# H-00488_-_USB_Hub.net
KiCad netlist of a schematic drawn in Altium Designer
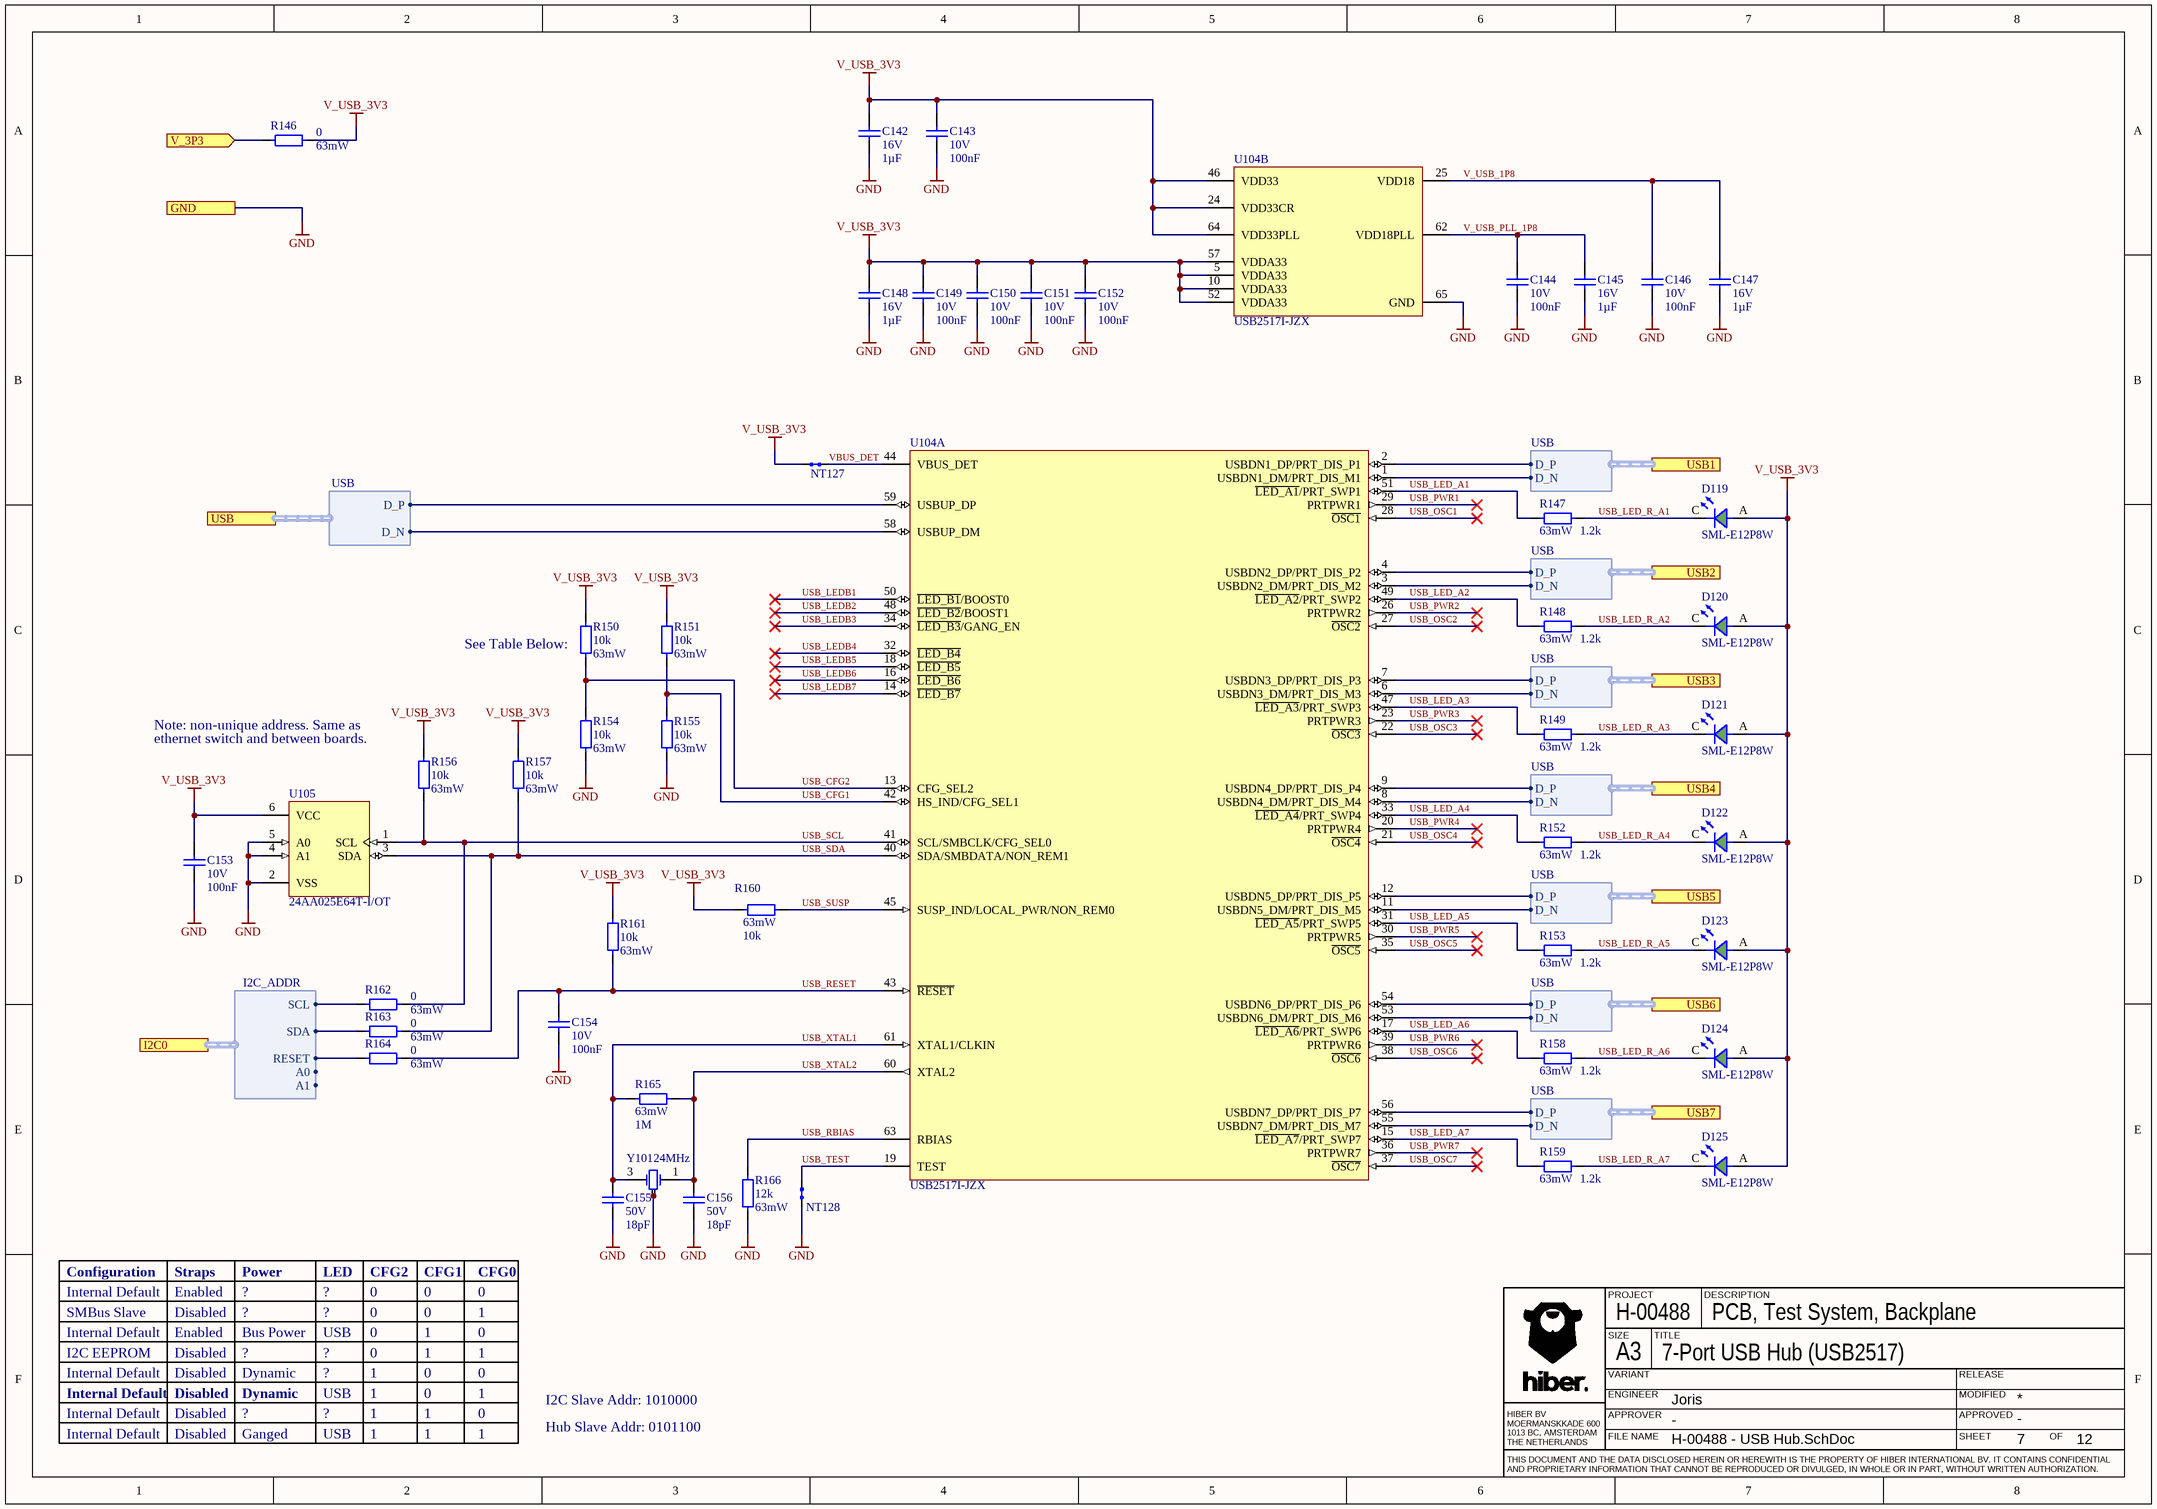
[diagram p0: H-00488 - USB Hub.SchDoc]

(export (version "E")
  (design (tool "Eeschema 10.0.6"))
  (components
    (comp (ref "C142")
      (value "1µF")
      (footprint "CAPC100X50X55L30N")
      (description "CAP Standard 0402 (1005) 1,0uF 16V X5R (Standard)")
      (fields
        (field (name "RATED VOLTAGE") "16V")
        (field (name "TOLERANCE") "10%")
        (field (name "Comment") "C0402C105K4PACTU")
      )
      (libsource (lib "Hiber") (part "CAPACITOR"))
    )
    (comp (ref "C143")
      (value "100nF")
      (footprint "CAPC100X50X55L30N")
      (description "CAP Standard 0402 (1005) 100,0nF 10V X7R (Standard)")
      (fields
        (field (name "RATED VOLTAGE") "10V")
        (field (name "TOLERANCE") "10%")
        (field (name "Comment") "C0402C104K8RACTU")
      )
      (libsource (lib "Hiber Vault") (part "CAPACITOR"))
    )
    (comp (ref "C144")
      (value "100nF")
      (footprint "CAPC100X50X55L30N")
      (description "CAP Standard 0402 (1005) 100,0nF 10V X7R (Standard)")
      (fields
        (field (name "RATED VOLTAGE") "10V")
        (field (name "TOLERANCE") "10%")
        (field (name "Comment") "C0402C104K8RACTU")
      )
      (libsource (lib "Hiber Vault") (part "CAPACITOR"))
    )
    (comp (ref "C145")
      (value "1µF")
      (footprint "CAPC100X50X55L30N")
      (description "CAP Standard 0402 (1005) 1,0uF 16V X5R (Standard)")
      (fields
        (field (name "RATED VOLTAGE") "16V")
        (field (name "TOLERANCE") "10%")
        (field (name "Comment") "C0402C105K4PACTU")
      )
      (libsource (lib "Hiber") (part "CAPACITOR"))
    )
    (comp (ref "C146")
      (value "100nF")
      (footprint "CAPC100X50X55L30N")
      (description "CAP Standard 0402 (1005) 100,0nF 10V X7R (Standard)")
      (fields
        (field (name "RATED VOLTAGE") "10V")
        (field (name "TOLERANCE") "10%")
        (field (name "Comment") "C0402C104K8RACTU")
      )
      (libsource (lib "Hiber Vault") (part "CAPACITOR"))
    )
    (comp (ref "C147")
      (value "1µF")
      (footprint "CAPC100X50X55L30N")
      (description "CAP Standard 0402 (1005) 1,0uF 16V X5R (Standard)")
      (fields
        (field (name "RATED VOLTAGE") "16V")
        (field (name "TOLERANCE") "10%")
        (field (name "Comment") "C0402C105K4PACTU")
      )
      (libsource (lib "Hiber") (part "CAPACITOR"))
    )
    (comp (ref "C148")
      (value "1µF")
      (footprint "CAPC100X50X55L30N")
      (description "CAP Standard 0402 (1005) 1,0uF 16V X5R (Standard)")
      (fields
        (field (name "RATED VOLTAGE") "16V")
        (field (name "TOLERANCE") "10%")
        (field (name "Comment") "C0402C105K4PACTU")
      )
      (libsource (lib "Hiber") (part "CAPACITOR"))
    )
    (comp (ref "C149")
      (value "100nF")
      (footprint "CAPC100X50X55L30N")
      (description "CAP Standard 0402 (1005) 100,0nF 10V X7R (Standard)")
      (fields
        (field (name "RATED VOLTAGE") "10V")
        (field (name "TOLERANCE") "10%")
        (field (name "Comment") "C0402C104K8RACTU")
      )
      (libsource (lib "Hiber Vault") (part "CAPACITOR"))
    )
    (comp (ref "C150")
      (value "100nF")
      (footprint "CAPC100X50X55L30N")
      (description "CAP Standard 0402 (1005) 100,0nF 10V X7R (Standard)")
      (fields
        (field (name "RATED VOLTAGE") "10V")
        (field (name "TOLERANCE") "10%")
        (field (name "Comment") "C0402C104K8RACTU")
      )
      (libsource (lib "Hiber Vault") (part "CAPACITOR"))
    )
    (comp (ref "C151")
      (value "100nF")
      (footprint "CAPC100X50X55L30N")
      (description "CAP Standard 0402 (1005) 100,0nF 10V X7R (Standard)")
      (fields
        (field (name "RATED VOLTAGE") "10V")
        (field (name "TOLERANCE") "10%")
        (field (name "Comment") "C0402C104K8RACTU")
      )
      (libsource (lib "Hiber Vault") (part "CAPACITOR"))
    )
    (comp (ref "C152")
      (value "100nF")
      (footprint "CAPC100X50X55L30N")
      (description "CAP Standard 0402 (1005) 100,0nF 10V X7R (Standard)")
      (fields
        (field (name "RATED VOLTAGE") "10V")
        (field (name "TOLERANCE") "10%")
        (field (name "Comment") "C0402C104K8RACTU")
      )
      (libsource (lib "Hiber Vault") (part "CAPACITOR"))
    )
    (comp (ref "C153")
      (value "100nF")
      (footprint "CAPC100X50X55L30N")
      (description "CAP Standard 0402 (1005) 100,0nF 10V X7R (Standard)")
      (fields
        (field (name "RATED VOLTAGE") "10V")
        (field (name "TOLERANCE") "10%")
        (field (name "Comment") "C0402C104K8RACTU")
      )
      (libsource (lib "Hiber Vault") (part "CAPACITOR"))
    )
    (comp (ref "C154")
      (value "100nF")
      (footprint "CAPC100X50X55L30N")
      (description "CAP Standard 0402 (1005) 100,0nF 10V X7R (Standard)")
      (fields
        (field (name "RATED VOLTAGE") "10V")
        (field (name "TOLERANCE") "10%")
        (field (name "Comment") "C0402C104K8RACTU")
      )
      (libsource (lib "Hiber Vault") (part "CAPACITOR"))
    )
    (comp (ref "C155")
      (value "18pF")
      (footprint "CAPC100X50X55L30N")
      (description "CAP Standard 0402 (1005) 18,0pF 50V C0G (Standard)")
      (fields
        (field (name "RATED VOLTAGE") "50V")
        (field (name "TOLERANCE") "5%")
        (field (name "Comment") "C0402C180J5GACTU")
      )
      (libsource (lib "Hiber") (part "CAPACITOR"))
    )
    (comp (ref "C156")
      (value "18pF")
      (footprint "CAPC100X50X55L30N")
      (description "CAP Standard 0402 (1005) 18,0pF 50V C0G (Standard)")
      (fields
        (field (name "RATED VOLTAGE") "50V")
        (field (name "TOLERANCE") "5%")
        (field (name "Comment") "C0402C180J5GACTU")
      )
      (libsource (lib "Hiber") (part "CAPACITOR"))
    )
    (comp (ref "D119")
      (value "SML-E12P8W")
      (footprint "LEDC170X80X80L20_GREEN")
      (description "LED Green Diffused 0603 SMD")
      (libsource (lib "Hiber") (part "DIODE-LED-GREEN"))
    )
    (comp (ref "D120")
      (value "SML-E12P8W")
      (footprint "LEDC170X80X80L20_GREEN")
      (description "LED Green Diffused 0603 SMD")
      (libsource (lib "Hiber") (part "DIODE-LED-GREEN"))
    )
    (comp (ref "D121")
      (value "SML-E12P8W")
      (footprint "LEDC170X80X80L20_GREEN")
      (description "LED Green Diffused 0603 SMD")
      (libsource (lib "Hiber") (part "DIODE-LED-GREEN"))
    )
    (comp (ref "D122")
      (value "SML-E12P8W")
      (footprint "LEDC170X80X80L20_GREEN")
      (description "LED Green Diffused 0603 SMD")
      (libsource (lib "Hiber") (part "DIODE-LED-GREEN"))
    )
    (comp (ref "D123")
      (value "SML-E12P8W")
      (footprint "LEDC170X80X80L20_GREEN")
      (description "LED Green Diffused 0603 SMD")
      (libsource (lib "Hiber") (part "DIODE-LED-GREEN"))
    )
    (comp (ref "D124")
      (value "SML-E12P8W")
      (footprint "LEDC170X80X80L20_GREEN")
      (description "LED Green Diffused 0603 SMD")
      (libsource (lib "Hiber") (part "DIODE-LED-GREEN"))
    )
    (comp (ref "D125")
      (value "SML-E12P8W")
      (footprint "LEDC170X80X80L20_GREEN")
      (description "LED Green Diffused 0603 SMD")
      (libsource (lib "Hiber") (part "DIODE-LED-GREEN"))
    )
    (comp (ref "NT127")
      (value "NET-TIE")
      (footprint "NT200")
      (description "Net Tie, Inline")
      (libsource (lib "Hiber") (part "NET-TIE"))
    )
    (comp (ref "NT128")
      (value "NET-TIE")
      (footprint "NT200")
      (description "Net Tie, Inline")
      (libsource (lib "Hiber") (part "NET-TIE"))
    )
    (comp (ref "R146")
      (value "0")
      (footprint "RESC100X50X40L25N")
      (description "RES Standard Thick Film 0402 0R00 ±1% 0,063W")
      (fields
        (field (name "TOLERANCE") "1%")
        (field (name "RATED POWER") "63mW")
        (field (name "Comment") "CRCW04020000Z0ED")
      )
      (libsource (lib "Hiber") (part "RESISTOR-2P"))
    )
    (comp (ref "R147")
      (value "1.2k")
      (footprint "RESC100X50X40L25N")
      (description "RES Standard Thick Film 0402 1K20 ±1% 0,063W")
      (fields
        (field (name "RATED POWER") "63mW")
        (field (name "TOLERANCE") "1%")
        (field (name "Comment") "CRCW04021K20FKED")
      )
      (libsource (lib "Hiber") (part "RESISTOR-2P"))
    )
    (comp (ref "R148")
      (value "1.2k")
      (footprint "RESC100X50X40L25N")
      (description "RES Standard Thick Film 0402 1K20 ±1% 0,063W")
      (fields
        (field (name "RATED POWER") "63mW")
        (field (name "TOLERANCE") "1%")
        (field (name "Comment") "CRCW04021K20FKED")
      )
      (libsource (lib "Hiber") (part "RESISTOR-2P"))
    )
    (comp (ref "R149")
      (value "1.2k")
      (footprint "RESC100X50X40L25N")
      (description "RES Standard Thick Film 0402 1K20 ±1% 0,063W")
      (fields
        (field (name "RATED POWER") "63mW")
        (field (name "TOLERANCE") "1%")
        (field (name "Comment") "CRCW04021K20FKED")
      )
      (libsource (lib "Hiber") (part "RESISTOR-2P"))
    )
    (comp (ref "R150")
      (value "10k")
      (footprint "RESC100X50X40L25N")
      (description "RES Standard Thick Film 0402 10K0 ±1% 0,063W")
      (fields
        (field (name "TOLERANCE") "1%")
        (field (name "RATED POWER") "63mW")
        (field (name "Comment") "CRCW040210K0FKED")
      )
      (libsource (lib "Hiber") (part "RESISTOR-2P"))
    )
    (comp (ref "R151")
      (value "10k")
      (footprint "RESC100X50X40L25N")
      (description "RES Standard Thick Film 0402 10K0 ±1% 0,063W")
      (fields
        (field (name "TOLERANCE") "1%")
        (field (name "RATED POWER") "63mW")
        (field (name "Comment") "CRCW040210K0FKED")
      )
      (libsource (lib "Hiber") (part "RESISTOR-2P"))
    )
    (comp (ref "R152")
      (value "1.2k")
      (footprint "RESC100X50X40L25N")
      (description "RES Standard Thick Film 0402 1K20 ±1% 0,063W")
      (fields
        (field (name "RATED POWER") "63mW")
        (field (name "TOLERANCE") "1%")
        (field (name "Comment") "CRCW04021K20FKED")
      )
      (libsource (lib "Hiber") (part "RESISTOR-2P"))
    )
    (comp (ref "R153")
      (value "1.2k")
      (footprint "RESC100X50X40L25N")
      (description "RES Standard Thick Film 0402 1K20 ±1% 0,063W")
      (fields
        (field (name "RATED POWER") "63mW")
        (field (name "TOLERANCE") "1%")
        (field (name "Comment") "CRCW04021K20FKED")
      )
      (libsource (lib "Hiber") (part "RESISTOR-2P"))
    )
    (comp (ref "R154")
      (value "10k")
      (footprint "RESC100X50X40L25N")
      (description "RES Standard Thick Film 0402 10K0 ±1% 0,063W")
      (fields
        (field (name "TOLERANCE") "1%")
        (field (name "RATED POWER") "63mW")
        (field (name "Comment") "CRCW040210K0FKED")
      )
      (libsource (lib "Hiber") (part "RESISTOR-2P"))
    )
    (comp (ref "R155")
      (value "10k")
      (footprint "RESC100X50X40L25N")
      (description "RES Standard Thick Film 0402 10K0 ±1% 0,063W")
      (fields
        (field (name "TOLERANCE") "1%")
        (field (name "RATED POWER") "63mW")
        (field (name "Comment") "CRCW040210K0FKED")
      )
      (libsource (lib "Hiber") (part "RESISTOR-2P"))
    )
    (comp (ref "R156")
      (value "10k")
      (footprint "RESC100X50X40L25N")
      (description "RES Standard Thick Film 0402 10K0 ±1% 0,063W")
      (fields
        (field (name "TOLERANCE") "1%")
        (field (name "RATED POWER") "63mW")
        (field (name "Comment") "CRCW040210K0FKED")
      )
      (libsource (lib "Hiber") (part "RESISTOR-2P"))
    )
    (comp (ref "R157")
      (value "10k")
      (footprint "RESC100X50X40L25N")
      (description "RES Standard Thick Film 0402 10K0 ±1% 0,063W")
      (fields
        (field (name "TOLERANCE") "1%")
        (field (name "RATED POWER") "63mW")
        (field (name "Comment") "CRCW040210K0FKED")
      )
      (libsource (lib "Hiber") (part "RESISTOR-2P"))
    )
    (comp (ref "R158")
      (value "1.2k")
      (footprint "RESC100X50X40L25N")
      (description "RES Standard Thick Film 0402 1K20 ±1% 0,063W")
      (fields
        (field (name "RATED POWER") "63mW")
        (field (name "TOLERANCE") "1%")
        (field (name "Comment") "CRCW04021K20FKED")
      )
      (libsource (lib "Hiber") (part "RESISTOR-2P"))
    )
    (comp (ref "R159")
      (value "1.2k")
      (footprint "RESC100X50X40L25N")
      (description "RES Standard Thick Film 0402 1K20 ±1% 0,063W")
      (fields
        (field (name "RATED POWER") "63mW")
        (field (name "TOLERANCE") "1%")
        (field (name "Comment") "CRCW04021K20FKED")
      )
      (libsource (lib "Hiber") (part "RESISTOR-2P"))
    )
    (comp (ref "R160")
      (value "10k")
      (footprint "RESC100X50X40L25N")
      (description "RES Standard Thick Film 0402 10K0 ±1% 0,063W")
      (fields
        (field (name "TOLERANCE") "1%")
        (field (name "RATED POWER") "63mW")
        (field (name "Comment") "CRCW040210K0FKED")
      )
      (libsource (lib "Hiber") (part "RESISTOR-2P"))
    )
    (comp (ref "R161")
      (value "10k")
      (footprint "RESC100X50X40L25N")
      (description "RES Standard Thick Film 0402 10K0 ±1% 0,063W")
      (fields
        (field (name "TOLERANCE") "1%")
        (field (name "RATED POWER") "63mW")
        (field (name "Comment") "CRCW040210K0FKED")
      )
      (libsource (lib "Hiber") (part "RESISTOR-2P"))
    )
    (comp (ref "R162")
      (value "0")
      (footprint "RESC100X50X40L25N")
      (description "RES Standard Thick Film 0402 0R00 ±1% 0,063W")
      (fields
        (field (name "TOLERANCE") "1%")
        (field (name "RATED POWER") "63mW")
        (field (name "Comment") "CRCW04020000Z0ED")
      )
      (libsource (lib "Hiber") (part "RESISTOR-2P"))
    )
    (comp (ref "R163")
      (value "0")
      (footprint "RESC100X50X40L25N")
      (description "RES Standard Thick Film 0402 0R00 ±1% 0,063W")
      (fields
        (field (name "TOLERANCE") "1%")
        (field (name "RATED POWER") "63mW")
        (field (name "Comment") "CRCW04020000Z0ED")
      )
      (libsource (lib "Hiber") (part "RESISTOR-2P"))
    )
    (comp (ref "R164")
      (value "0")
      (footprint "RESC100X50X40L25N")
      (description "RES Standard Thick Film 0402 0R00 ±1% 0,063W")
      (fields
        (field (name "TOLERANCE") "1%")
        (field (name "RATED POWER") "63mW")
        (field (name "Comment") "CRCW04020000Z0ED")
      )
      (libsource (lib "Hiber") (part "RESISTOR-2P"))
    )
    (comp (ref "R165")
      (value "1M")
      (footprint "RESC100X50X40L25N")
      (description "RES Standard Thick Film 0402 1M00 ±1% 0,063W")
      (fields
        (field (name "RATED POWER") "63mW")
        (field (name "TOLERANCE") "1%")
        (field (name "Comment") "CRCW04021M00FKED")
      )
      (libsource (lib "Hiber") (part "RESISTOR-2P"))
    )
    (comp (ref "R166")
      (value "12k")
      (footprint "RESC100X50X40L25N")
      (description "RES Standard Thick Film 0402 12K0 ±1% 0,063W")
      (fields
        (field (name "TOLERANCE") "1%")
        (field (name "RATED POWER") "63mW")
        (field (name "Comment") "CRCW040212K0FKED")
      )
      (libsource (lib "Hiber") (part "RESISTOR-2P"))
    )
    (comp (ref "U104")
      (value "USB2517I-JZX")
      (footprint "QFN65P50_900X900X100L40X24T470N")
      (description "USB Bus Controller, CMOS")
      (libsource (lib "Hiber") (part "USB2517"))
    )
    (comp (ref "U105")
      (value "24AA025E64T-I/OT")
      (footprint "SOT23-6P95_270X145L35X35")
      (description "EEPROM, 256X8, Serial, CMOS, PDSO5")
      (libsource (lib "Hiber") (part "MCHP-24AA025E64_025UID-SOT-23-6"))
    )
    (comp (ref "Y101")
      (value "TSX-322524.0000MF15X-AC3")
      (footprint "OSCCC320X250X60L90X110")
      (description "Parallel - Fundamental Quartz Crystal, 24MHz Nom")
      (fields (field (name "FREQUENCY") "24MHz") (field (name "TOLERANCE") "10ppm"))
      (libsource (lib "Hiber") (part "CRYSTAL-4P"))
    )
  )
  (nets
    (net (code "3") (name "/RESET") (class "Default")
      (node (ref "R164") (pin "1") (pinfunction "1_1") (pintype "passive"))
    )
    (net (code "4") (name "/SCL") (class "Default")
      (node (ref "R162") (pin "1") (pinfunction "1_1") (pintype "passive"))
    )
    (net (code "5") (name "/SDA") (class "Default")
      (node (ref "R163") (pin "2") (pinfunction "2_2") (pintype "passive"))
    )
    (net (code "6") (name "/USB_CFG1") (class "Default")
      (node (ref "R151") (pin "2") (pinfunction "2_2") (pintype "passive"))
      (node (ref "R155") (pin "1") (pinfunction "1_1") (pintype "passive"))
      (node (ref "U104") (pin "42") (pinfunction "HS_IND/CFG_SEL1_42") (pintype "bidirectional"))
    )
    (net (code "7") (name "/USB_CFG2") (class "Default")
      (node (ref "R150") (pin "2") (pinfunction "2_2") (pintype "passive"))
      (node (ref "R154") (pin "1") (pinfunction "1_1") (pintype "passive"))
      (node (ref "U104") (pin "13") (pinfunction "CFG_SEL2_13") (pintype "bidirectional"))
    )
    (net (code "8") (name "/USB_LEDB1") (class "Default")
      (node (ref "U104") (pin "50") (pinfunction "~{LED_B1}/BOOST0_50") (pintype "bidirectional+no_connect"))
    )
    (net (code "9") (name "/USB_LEDB2") (class "Default")
      (node (ref "U104") (pin "48") (pinfunction "~{LED_B2}/BOOST1_48") (pintype "bidirectional+no_connect"))
    )
    (net (code "10") (name "/USB_LEDB3") (class "Default")
      (node (ref "U104") (pin "34") (pinfunction "~{LED_B3}/GANG_EN_34") (pintype "bidirectional+no_connect"))
    )
    (net (code "11") (name "/USB_LEDB4") (class "Default")
      (node (ref "U104") (pin "32") (pinfunction "~{LED_B4}_32") (pintype "bidirectional+no_connect"))
    )
    (net (code "12") (name "/USB_LEDB5") (class "Default")
      (node (ref "U104") (pin "18") (pinfunction "~{LED_B5}_18") (pintype "bidirectional+no_connect"))
    )
    (net (code "13") (name "/USB_LEDB6") (class "Default")
      (node (ref "U104") (pin "16") (pinfunction "~{LED_B6}_16") (pintype "bidirectional+no_connect"))
    )
    (net (code "14") (name "/USB_LEDB7") (class "Default")
      (node (ref "U104") (pin "14") (pinfunction "~{LED_B7}_14") (pintype "bidirectional+no_connect"))
    )
    (net (code "15") (name "/USB_LED_A1") (class "Default")
      (node (ref "R147") (pin "2") (pinfunction "2_2") (pintype "passive"))
      (node (ref "U104") (pin "51") (pinfunction "~{LED_A1}/PRT_SWP1_51") (pintype "bidirectional"))
    )
    (net (code "16") (name "/USB_LED_A2") (class "Default")
      (node (ref "R148") (pin "2") (pinfunction "2_2") (pintype "passive"))
      (node (ref "U104") (pin "49") (pinfunction "~{LED_A2}/PRT_SWP2_49") (pintype "bidirectional"))
    )
    (net (code "17") (name "/USB_LED_A3") (class "Default")
      (node (ref "R149") (pin "2") (pinfunction "2_2") (pintype "passive"))
      (node (ref "U104") (pin "47") (pinfunction "~{LED_A3}/PRT_SWP3_47") (pintype "bidirectional"))
    )
    (net (code "18") (name "/USB_LED_A4") (class "Default")
      (node (ref "R152") (pin "2") (pinfunction "2_2") (pintype "passive"))
      (node (ref "U104") (pin "33") (pinfunction "~{LED_A4}/PRT_SWP4_33") (pintype "bidirectional"))
    )
    (net (code "19") (name "/USB_LED_A5") (class "Default")
      (node (ref "R153") (pin "2") (pinfunction "2_2") (pintype "passive"))
      (node (ref "U104") (pin "31") (pinfunction "~{LED_A5}/PRT_SWP5_31") (pintype "bidirectional"))
    )
    (net (code "20") (name "/USB_LED_A6") (class "Default")
      (node (ref "R158") (pin "2") (pinfunction "2_2") (pintype "passive"))
      (node (ref "U104") (pin "17") (pinfunction "~{LED_A6}/PRT_SWP6_17") (pintype "bidirectional"))
    )
    (net (code "21") (name "/USB_LED_A7") (class "Default")
      (node (ref "R159") (pin "2") (pinfunction "2_2") (pintype "passive"))
      (node (ref "U104") (pin "15") (pinfunction "~{LED_A7}/PRT_SWP7_15") (pintype "bidirectional"))
    )
    (net (code "22") (name "/USB_LED_R_A1") (class "Default")
      (node (ref "D119") (pin "C") (pinfunction "C_C") (pintype "passive"))
      (node (ref "R147") (pin "1") (pinfunction "1_1") (pintype "passive"))
    )
    (net (code "23") (name "/USB_LED_R_A2") (class "Default")
      (node (ref "D120") (pin "C") (pinfunction "C_C") (pintype "passive"))
      (node (ref "R148") (pin "1") (pinfunction "1_1") (pintype "passive"))
    )
    (net (code "24") (name "/USB_LED_R_A3") (class "Default")
      (node (ref "D121") (pin "C") (pinfunction "C_C") (pintype "passive"))
      (node (ref "R149") (pin "1") (pinfunction "1_1") (pintype "passive"))
    )
    (net (code "25") (name "/USB_LED_R_A4") (class "Default")
      (node (ref "D122") (pin "C") (pinfunction "C_C") (pintype "passive"))
      (node (ref "R152") (pin "1") (pinfunction "1_1") (pintype "passive"))
    )
    (net (code "26") (name "/USB_LED_R_A5") (class "Default")
      (node (ref "D123") (pin "C") (pinfunction "C_C") (pintype "passive"))
      (node (ref "R153") (pin "1") (pinfunction "1_1") (pintype "passive"))
    )
    (net (code "27") (name "/USB_LED_R_A6") (class "Default")
      (node (ref "D124") (pin "C") (pinfunction "C_C") (pintype "passive"))
      (node (ref "R158") (pin "1") (pinfunction "1_1") (pintype "passive"))
    )
    (net (code "28") (name "/USB_LED_R_A7") (class "Default")
      (node (ref "D125") (pin "C") (pinfunction "C_C") (pintype "passive"))
      (node (ref "R159") (pin "1") (pinfunction "1_1") (pintype "passive"))
    )
    (net (code "29") (name "/USB_OSC1") (class "Default")
      (node (ref "U104") (pin "28") (pinfunction "~{OSC1}_28") (pintype "input+no_connect"))
    )
    (net (code "30") (name "/USB_OSC2") (class "Default")
      (node (ref "U104") (pin "27") (pinfunction "~{OSC2}_27") (pintype "input+no_connect"))
    )
    (net (code "31") (name "/USB_OSC3") (class "Default")
      (node (ref "U104") (pin "22") (pinfunction "~{OSC3}_22") (pintype "input+no_connect"))
    )
    (net (code "32") (name "/USB_OSC4") (class "Default")
      (node (ref "U104") (pin "21") (pinfunction "~{OSC4}_21") (pintype "input+no_connect"))
    )
    (net (code "33") (name "/USB_OSC5") (class "Default")
      (node (ref "U104") (pin "35") (pinfunction "~{OSC5}_35") (pintype "input+no_connect"))
    )
    (net (code "34") (name "/USB_OSC6") (class "Default")
      (node (ref "U104") (pin "38") (pinfunction "~{OSC6}_38") (pintype "input+no_connect"))
    )
    (net (code "35") (name "/USB_OSC7") (class "Default")
      (node (ref "U104") (pin "37") (pinfunction "~{OSC7}_37") (pintype "input+no_connect"))
    )
    (net (code "36") (name "/USB_PWR1") (class "Default")
      (node (ref "U104") (pin "29") (pinfunction "PRTPWR1_29") (pintype "output+no_connect"))
    )
    (net (code "37") (name "/USB_PWR2") (class "Default")
      (node (ref "U104") (pin "26") (pinfunction "PRTPWR2_26") (pintype "output+no_connect"))
    )
    (net (code "38") (name "/USB_PWR3") (class "Default")
      (node (ref "U104") (pin "23") (pinfunction "PRTPWR3_23") (pintype "output+no_connect"))
    )
    (net (code "39") (name "/USB_PWR4") (class "Default")
      (node (ref "U104") (pin "20") (pinfunction "PRTPWR4_20") (pintype "output+no_connect"))
    )
    (net (code "40") (name "/USB_PWR5") (class "Default")
      (node (ref "U104") (pin "30") (pinfunction "PRTPWR5_30") (pintype "output+no_connect"))
    )
    (net (code "41") (name "/USB_PWR6") (class "Default")
      (node (ref "U104") (pin "39") (pinfunction "PRTPWR6_39") (pintype "output+no_connect"))
    )
    (net (code "42") (name "/USB_PWR7") (class "Default")
      (node (ref "U104") (pin "36") (pinfunction "PRTPWR7_36") (pintype "output+no_connect"))
    )
    (net (code "43") (name "/USB_RBIAS") (class "Default")
      (node (ref "R166") (pin "2") (pinfunction "2_2") (pintype "passive"))
      (node (ref "U104") (pin "63") (pinfunction "RBIAS_63") (pintype "passive"))
    )
    (net (code "44") (name "/USB_RESET") (class "Default")
      (node (ref "C154") (pin "1") (pinfunction "1_1") (pintype "passive"))
      (node (ref "R161") (pin "2") (pinfunction "2_2") (pintype "passive"))
      (node (ref "R164") (pin "2") (pinfunction "2_2") (pintype "passive"))
      (node (ref "U104") (pin "43") (pinfunction "~{RESET}_43") (pintype "input"))
    )
    (net (code "45") (name "/USB_SCL") (class "Default")
      (node (ref "R156") (pin "2") (pinfunction "2_2") (pintype "passive"))
      (node (ref "R162") (pin "2") (pinfunction "2_2") (pintype "passive"))
      (node (ref "U104") (pin "41") (pinfunction "SCL/SMBCLK/CFG_SEL0_41") (pintype "bidirectional"))
      (node (ref "U105") (pin "1") (pinfunction "SCL_1") (pintype "input"))
    )
    (net (code "46") (name "/USB_SDA") (class "Default")
      (node (ref "R157") (pin "2") (pinfunction "2_2") (pintype "passive"))
      (node (ref "R163") (pin "1") (pinfunction "1_1") (pintype "passive"))
      (node (ref "U104") (pin "40") (pinfunction "SDA/SMBDATA/NON_REM1_40") (pintype "bidirectional"))
      (node (ref "U105") (pin "3") (pinfunction "SDA_3") (pintype "bidirectional"))
    )
    (net (code "47") (name "/USB_SUSP") (class "Default")
      (node (ref "R160") (pin "2") (pinfunction "2_2") (pintype "passive"))
      (node (ref "U104") (pin "45") (pinfunction "SUSP_IND/LOCAL_PWR/NON_REM0_45") (pintype "input"))
    )
    (net (code "48") (name "/USB_TEST") (class "Default")
      (node (ref "NT128") (pin "1") (pinfunction "1_1") (pintype "passive"))
      (node (ref "U104") (pin "19") (pinfunction "TEST_19") (pintype "passive"))
    )
    (net (code "49") (name "/USB_XTAL1") (class "Default")
      (node (ref "C155") (pin "1") (pinfunction "1_1") (pintype "passive"))
      (node (ref "R165") (pin "1") (pinfunction "1_1") (pintype "passive"))
      (node (ref "U104") (pin "61") (pinfunction "XTAL1/CLKIN_61") (pintype "input"))
      (node (ref "Y101") (pin "3") (pinfunction "3_3") (pintype "passive"))
    )
    (net (code "50") (name "/USB_XTAL2") (class "Default")
      (node (ref "C156") (pin "1") (pinfunction "1_1") (pintype "passive"))
      (node (ref "R165") (pin "2") (pinfunction "2_2") (pintype "passive"))
      (node (ref "U104") (pin "60") (pinfunction "XTAL2_60") (pintype "output"))
      (node (ref "Y101") (pin "1") (pinfunction "1_1") (pintype "passive"))
    )
    (net (code "51") (name "/VBUS_DET") (class "Default")
      (node (ref "NT127") (pin "2") (pinfunction "1_2") (pintype "passive"))
      (node (ref "U104") (pin "44") (pinfunction "VBUS_DET_44") (pintype "power_in"))
    )
    (net (code "52") (name "/V_3P3") (class "Default")
      (node (ref "R146") (pin "1") (pinfunction "1_1") (pintype "passive"))
    )
    (net (code "53") (name "/V_USB_1P8") (class "Default")
      (node (ref "C146") (pin "1") (pinfunction "1_1") (pintype "passive"))
      (node (ref "C147") (pin "2") (pinfunction "2_2") (pintype "passive"))
      (node (ref "U104") (pin "25") (pinfunction "VDD18_25") (pintype "power_in"))
    )
    (net (code "54") (name "/V_USB_PLL_1P8") (class "Default")
      (node (ref "C144") (pin "1") (pinfunction "1_1") (pintype "passive"))
      (node (ref "C145") (pin "2") (pinfunction "2_2") (pintype "passive"))
      (node (ref "U104") (pin "62") (pinfunction "VDD18PLL_62") (pintype "power_in"))
    )
    (net (code "57") (name "GND") (class "Default")
      (node (ref "C142") (pin "1") (pinfunction "1_1") (pintype "passive"))
      (node (ref "C143") (pin "2") (pinfunction "2_2") (pintype "passive"))
      (node (ref "C144") (pin "2") (pinfunction "2_2") (pintype "passive"))
      (node (ref "C145") (pin "1") (pinfunction "1_1") (pintype "passive"))
      (node (ref "C146") (pin "2") (pinfunction "2_2") (pintype "passive"))
      (node (ref "C147") (pin "1") (pinfunction "1_1") (pintype "passive"))
      (node (ref "C148") (pin "1") (pinfunction "1_1") (pintype "passive"))
      (node (ref "C149") (pin "2") (pinfunction "2_2") (pintype "passive"))
      (node (ref "C150") (pin "2") (pinfunction "2_2") (pintype "passive"))
      (node (ref "C151") (pin "2") (pinfunction "2_2") (pintype "passive"))
      (node (ref "C152") (pin "2") (pinfunction "2_2") (pintype "passive"))
      (node (ref "C153") (pin "2") (pinfunction "2_2") (pintype "passive"))
      (node (ref "C154") (pin "2") (pinfunction "2_2") (pintype "passive"))
      (node (ref "C155") (pin "2") (pinfunction "2_2") (pintype "passive"))
      (node (ref "C156") (pin "2") (pinfunction "2_2") (pintype "passive"))
      (node (ref "NT128") (pin "2") (pinfunction "1_2") (pintype "passive"))
      (node (ref "R154") (pin "2") (pinfunction "2_2") (pintype "passive"))
      (node (ref "R155") (pin "2") (pinfunction "2_2") (pintype "passive"))
      (node (ref "R166") (pin "1") (pinfunction "1_1") (pintype "passive"))
      (node (ref "U104") (pin "65") (pinfunction "GND_65") (pintype "power_in"))
      (node (ref "U105") (pin "2") (pinfunction "VSS_2") (pintype "power_in"))
      (node (ref "U105") (pin "4") (pinfunction "A1_4") (pintype "input"))
      (node (ref "U105") (pin "5") (pinfunction "A0_5") (pintype "input"))
      (node (ref "Y101") (pin "2") (pinfunction "2_2") (pintype "passive"))
      (node (ref "Y101") (pin "4") (pinfunction "4_4") (pintype "passive"))
    )
    (net (code "58") (name "V_USB_3V3") (class "Default")
      (node (ref "C142") (pin "2") (pinfunction "2_2") (pintype "passive"))
      (node (ref "C143") (pin "1") (pinfunction "1_1") (pintype "passive"))
      (node (ref "C148") (pin "2") (pinfunction "2_2") (pintype "passive"))
      (node (ref "C149") (pin "1") (pinfunction "1_1") (pintype "passive"))
      (node (ref "C150") (pin "1") (pinfunction "1_1") (pintype "passive"))
      (node (ref "C151") (pin "1") (pinfunction "1_1") (pintype "passive"))
      (node (ref "C152") (pin "1") (pinfunction "1_1") (pintype "passive"))
      (node (ref "C153") (pin "1") (pinfunction "1_1") (pintype "passive"))
      (node (ref "D119") (pin "A") (pinfunction "A_A") (pintype "passive"))
      (node (ref "D120") (pin "A") (pinfunction "A_A") (pintype "passive"))
      (node (ref "D121") (pin "A") (pinfunction "A_A") (pintype "passive"))
      (node (ref "D122") (pin "A") (pinfunction "A_A") (pintype "passive"))
      (node (ref "D123") (pin "A") (pinfunction "A_A") (pintype "passive"))
      (node (ref "D124") (pin "A") (pinfunction "A_A") (pintype "passive"))
      (node (ref "D125") (pin "A") (pinfunction "A_A") (pintype "passive"))
      (node (ref "NT127") (pin "1") (pinfunction "1_1") (pintype "passive"))
      (node (ref "R146") (pin "2") (pinfunction "2_2") (pintype "passive"))
      (node (ref "R150") (pin "1") (pinfunction "1_1") (pintype "passive"))
      (node (ref "R151") (pin "1") (pinfunction "1_1") (pintype "passive"))
      (node (ref "R156") (pin "1") (pinfunction "1_1") (pintype "passive"))
      (node (ref "R157") (pin "1") (pinfunction "1_1") (pintype "passive"))
      (node (ref "R160") (pin "1") (pinfunction "1_1") (pintype "passive"))
      (node (ref "R161") (pin "1") (pinfunction "1_1") (pintype "passive"))
      (node (ref "U104") (pin "10") (pinfunction "VDDA33_10") (pintype "power_in"))
      (node (ref "U104") (pin "24") (pinfunction "VDD33CR_24") (pintype "power_in"))
      (node (ref "U104") (pin "46") (pinfunction "VDD33_46") (pintype "power_in"))
      (node (ref "U104") (pin "5") (pinfunction "VDDA33_5") (pintype "power_in"))
      (node (ref "U104") (pin "52") (pinfunction "VDDA33_52") (pintype "power_in"))
      (node (ref "U104") (pin "57") (pinfunction "VDDA33_57") (pintype "power_in"))
      (node (ref "U104") (pin "64") (pinfunction "VDD33PLL_64") (pintype "power_in"))
      (node (ref "U105") (pin "6") (pinfunction "VCC_6") (pintype "power_in"))
    )
    (net (code "59") (name "unconnected-(U104A-USBDN1_DM{slash}PRT_DIS_M1-Pad1)") (class "Default")
      (node (ref "U104") (pin "1") (pinfunction "USBDN1_DM/PRT_DIS_M1_1") (pintype "bidirectional"))
    )
    (net (code "60") (name "unconnected-(U104A-USBDN1_DP{slash}PRT_DIS_P1-Pad2)") (class "Default")
      (node (ref "U104") (pin "2") (pinfunction "USBDN1_DP/PRT_DIS_P1_2") (pintype "bidirectional"))
    )
    (net (code "61") (name "unconnected-(U104A-USBDN2_DM{slash}PRT_DIS_M2-Pad3)") (class "Default")
      (node (ref "U104") (pin "3") (pinfunction "USBDN2_DM/PRT_DIS_M2_3") (pintype "bidirectional"))
    )
    (net (code "62") (name "unconnected-(U104A-USBDN2_DP{slash}PRT_DIS_P2-Pad4)") (class "Default")
      (node (ref "U104") (pin "4") (pinfunction "USBDN2_DP/PRT_DIS_P2_4") (pintype "bidirectional"))
    )
    (net (code "63") (name "unconnected-(U104A-USBDN3_DM{slash}PRT_DIS_M3-Pad6)") (class "Default")
      (node (ref "U104") (pin "6") (pinfunction "USBDN3_DM/PRT_DIS_M3_6") (pintype "bidirectional"))
    )
    (net (code "64") (name "unconnected-(U104A-USBDN3_DP{slash}PRT_DIS_P3-Pad7)") (class "Default")
      (node (ref "U104") (pin "7") (pinfunction "USBDN3_DP/PRT_DIS_P3_7") (pintype "bidirectional"))
    )
    (net (code "65") (name "unconnected-(U104A-USBDN4_DM{slash}PRT_DIS_M4-Pad8)") (class "Default")
      (node (ref "U104") (pin "8") (pinfunction "USBDN4_DM/PRT_DIS_M4_8") (pintype "bidirectional"))
    )
    (net (code "66") (name "unconnected-(U104A-USBDN4_DP{slash}PRT_DIS_P4-Pad9)") (class "Default")
      (node (ref "U104") (pin "9") (pinfunction "USBDN4_DP/PRT_DIS_P4_9") (pintype "bidirectional"))
    )
    (net (code "67") (name "unconnected-(U104A-USBDN5_DM{slash}PRT_DIS_M5-Pad11)") (class "Default")
      (node (ref "U104") (pin "11") (pinfunction "USBDN5_DM/PRT_DIS_M5_11") (pintype "bidirectional"))
    )
    (net (code "68") (name "unconnected-(U104A-USBDN5_DP{slash}PRT_DIS_P5-Pad12)") (class "Default")
      (node (ref "U104") (pin "12") (pinfunction "USBDN5_DP/PRT_DIS_P5_12") (pintype "bidirectional"))
    )
    (net (code "69") (name "unconnected-(U104A-USBDN6_DM{slash}PRT_DIS_M6-Pad53)") (class "Default")
      (node (ref "U104") (pin "53") (pinfunction "USBDN6_DM/PRT_DIS_M6_53") (pintype "bidirectional"))
    )
    (net (code "70") (name "unconnected-(U104A-USBDN6_DP{slash}PRT_DIS_P6-Pad54)") (class "Default")
      (node (ref "U104") (pin "54") (pinfunction "USBDN6_DP/PRT_DIS_P6_54") (pintype "bidirectional"))
    )
    (net (code "71") (name "unconnected-(U104A-USBDN7_DM{slash}PRT_DIS_M7-Pad55)") (class "Default")
      (node (ref "U104") (pin "55") (pinfunction "USBDN7_DM/PRT_DIS_M7_55") (pintype "bidirectional"))
    )
    (net (code "72") (name "unconnected-(U104A-USBDN7_DP{slash}PRT_DIS_P7-Pad56)") (class "Default")
      (node (ref "U104") (pin "56") (pinfunction "USBDN7_DP/PRT_DIS_P7_56") (pintype "bidirectional"))
    )
    (net (code "73") (name "unconnected-(U104A-USBUP_DM-Pad58)") (class "Default")
      (node (ref "U104") (pin "58") (pinfunction "USBUP_DM_58") (pintype "bidirectional"))
    )
    (net (code "74") (name "unconnected-(U104A-USBUP_DP-Pad59)") (class "Default")
      (node (ref "U104") (pin "59") (pinfunction "USBUP_DP_59") (pintype "bidirectional"))
    )
  )
)
